# USB.net
KiCad netlist of a schematic drawn in Altium Designer
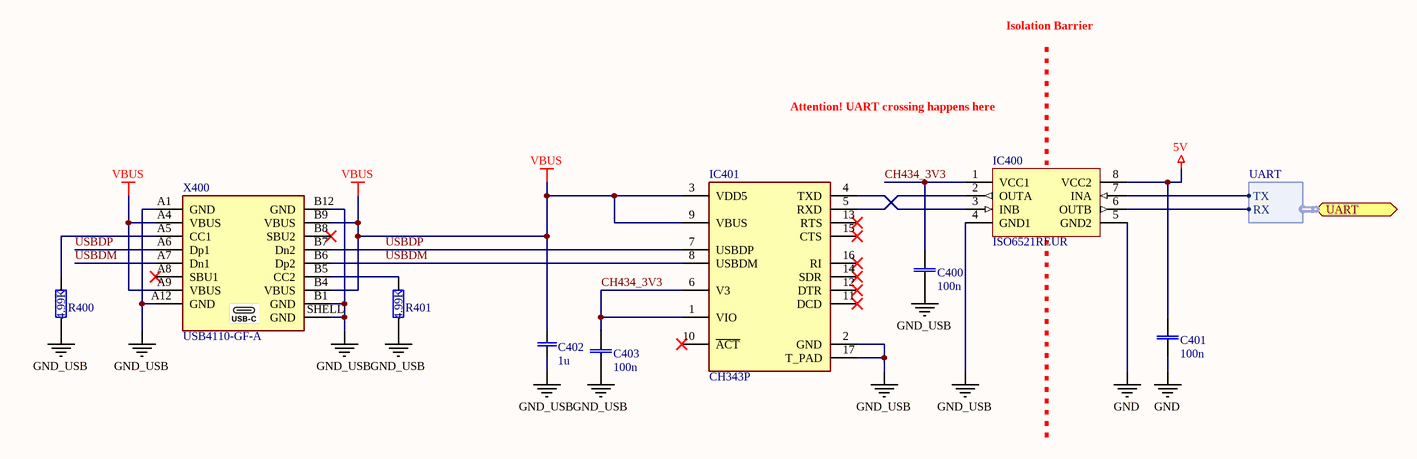
[diagram p0: USB.SchDoc]

(export (version "E")
  (design (tool "Eeschema 10.0.6"))
  (components
    (comp (ref "C400")
      (value "100n")
      (footprint "CAP0402")
      (fields (field (name "MPN") "CL05A104KA5NNNC") (field (name "TOLERANCE") "10%"))
      (libsource (lib "Schematic") (part "CL05A104KA5NNNC"))
    )
    (comp (ref "C401")
      (value "100n")
      (footprint "CAP0402")
      (fields (field (name "MPN") "CL05A104KA5NNNC") (field (name "TOLERANCE") "10%"))
      (libsource (lib "Schematic") (part "CL05A104KA5NNNC"))
    )
    (comp (ref "C402")
      (value "1u")
      (footprint "0603")
      (fields (field (name "PART NUMBER") "000088"))
      (libsource (lib "TychosLibrary") (part "Capacitor"))
    )
    (comp (ref "C403")
      (value "100n")
      (footprint "CAP0402")
      (fields (field (name "MPN") "CL05A104KA5NNNC") (field (name "TOLERANCE") "10%"))
      (libsource (lib "Schematic") (part "CL05A104KA5NNNC"))
    )
    (comp (ref "IC400")
      (value "ISO6521REUR")
      (footprint "VSON8(ISO6521REUR)")
      (libsource (lib "Schematic") (part "ISO6521REUR"))
    )
    (comp (ref "IC401")
      (value "CH343P")
      (footprint "QFN16_3X3")
      (fields (field (name "MANUFACTURER") "WCH") (field (name "JLCPCB PART #") "C2846043"))
      (libsource (lib "Schematic") (part "CH343P"))
    )
    (comp (ref "R400")
      (value "RC0402FR-074K99L")
      (footprint "RES0402")
      (libsource (lib "Passive") (part "RC0402FR-074K99L"))
    )
    (comp (ref "R401")
      (value "RC0402FR-074K99L")
      (footprint "RES0402")
      (libsource (lib "Passive") (part "RC0402FR-074K99L"))
    )
    (comp (ref "X400")
      (value "USB4110-GF-A")
      (footprint "USB4110")
      (libsource (lib "Schematic") (part "USB4110-GF-A"))
    )
  )
  (nets
    (net (code "2") (name "/CH434_3V3") (class "Default")
      (node (ref "C400") (pin "1") (pinfunction "1_1") (pintype "passive"))
      (node (ref "C403") (pin "1") (pinfunction "1_1") (pintype "passive"))
      (node (ref "IC400") (pin "1") (pinfunction "VCC1_1") (pintype "power_in"))
      (node (ref "IC401") (pin "1") (pinfunction "VIO_1") (pintype "passive"))
      (node (ref "IC401") (pin "6") (pinfunction "V3_6") (pintype "passive"))
    )
    (net (code "3") (name "/RX") (class "Default")
      (node (ref "IC400") (pin "6") (pinfunction "OUTB_6") (pintype "output"))
    )
    (net (code "4") (name "/TX") (class "Default")
      (node (ref "IC400") (pin "7") (pinfunction "INA_7") (pintype "input"))
    )
    (net (code "5") (name "/USBDM") (class "Default")
      (node (ref "IC401") (pin "8") (pinfunction "USBDM_8") (pintype "passive"))
      (node (ref "X400") (pin "A7") (pinfunction "Dn1_A7") (pintype "passive"))
      (node (ref "X400") (pin "B6") (pinfunction "Dp2_B6") (pintype "passive"))
    )
    (net (code "6") (name "/USBDP") (class "Default")
      (node (ref "IC401") (pin "7") (pinfunction "USBDP_7") (pintype "passive"))
      (node (ref "X400") (pin "A6") (pinfunction "Dp1_A6") (pintype "passive"))
      (node (ref "X400") (pin "B7") (pinfunction "Dn2_B7") (pintype "passive"))
    )
    (net (code "8") (name "5V") (class "Default")
      (node (ref "C401") (pin "1") (pinfunction "1_1") (pintype "passive"))
      (node (ref "IC400") (pin "8") (pinfunction "VCC2_8") (pintype "power_in"))
    )
    (net (code "9") (name "GND") (class "Default")
      (node (ref "C401") (pin "2") (pinfunction "2_2") (pintype "passive"))
      (node (ref "IC400") (pin "5") (pinfunction "GND2_5") (pintype "passive"))
    )
    (net (code "10") (name "GND_USB") (class "Default")
      (node (ref "C400") (pin "2") (pinfunction "2_2") (pintype "passive"))
      (node (ref "C402") (pin "1") (pinfunction "1_1") (pintype "passive"))
      (node (ref "C403") (pin "2") (pinfunction "2_2") (pintype "passive"))
      (node (ref "IC400") (pin "4") (pinfunction "GND1_4") (pintype "passive"))
      (node (ref "IC401") (pin "17") (pinfunction "T_PAD_17") (pintype "passive"))
      (node (ref "IC401") (pin "2") (pinfunction "GND_2") (pintype "passive"))
      (node (ref "R400") (pin "1") (pinfunction "1_1") (pintype "passive"))
      (node (ref "R401") (pin "1") (pinfunction "1_1") (pintype "passive"))
      (node (ref "X400") (pin "A1") (pinfunction "GND_A1") (pintype "passive"))
      (node (ref "X400") (pin "A12") (pinfunction "GND_A12") (pintype "passive"))
      (node (ref "X400") (pin "B1") (pinfunction "GND_B1") (pintype "passive"))
      (node (ref "X400") (pin "B12") (pinfunction "GND_B12") (pintype "passive"))
      (node (ref "X400") (pin "SHELL") (pinfunction "GND_SHELL") (pintype "passive"))
    )
    (net (code "11") (name "Net-(IC400-INB)") (class "Default")
      (node (ref "IC400") (pin "3") (pinfunction "INB_3") (pintype "input"))
      (node (ref "IC401") (pin "4") (pinfunction "TXD_4") (pintype "passive"))
    )
    (net (code "12") (name "Net-(IC400-OUTA)") (class "Default")
      (node (ref "IC400") (pin "2") (pinfunction "OUTA_2") (pintype "output"))
      (node (ref "IC401") (pin "5") (pinfunction "RXD_5") (pintype "passive"))
    )
    (net (code "13") (name "Net-(X400-CC1)") (class "Default")
      (node (ref "R400") (pin "2") (pinfunction "2_2") (pintype "passive"))
      (node (ref "X400") (pin "A5") (pinfunction "CC1_A5") (pintype "passive"))
    )
    (net (code "14") (name "Net-(X400-CC2)") (class "Default")
      (node (ref "R401") (pin "2") (pinfunction "2_2") (pintype "passive"))
      (node (ref "X400") (pin "B5") (pinfunction "CC2_B5") (pintype "passive"))
    )
    (net (code "15") (name "VBUS") (class "Default")
      (node (ref "C402") (pin "2") (pinfunction "2_2") (pintype "passive"))
      (node (ref "IC401") (pin "3") (pinfunction "VDD5_3") (pintype "passive"))
      (node (ref "IC401") (pin "9") (pinfunction "VBUS_9") (pintype "passive"))
      (node (ref "X400") (pin "A4") (pinfunction "VBUS_A4") (pintype "passive"))
      (node (ref "X400") (pin "A9") (pinfunction "VBUS_A9") (pintype "passive"))
      (node (ref "X400") (pin "B4") (pinfunction "VBUS_B4") (pintype "passive"))
      (node (ref "X400") (pin "B9") (pinfunction "VBUS_B9") (pintype "passive"))
    )
    (net (code "16") (name "unconnected-(IC401-CTS-Pad15)") (class "Default")
      (node (ref "IC401") (pin "15") (pinfunction "CTS_15") (pintype "passive+no_connect"))
    )
    (net (code "17") (name "unconnected-(IC401-DCD-Pad11)") (class "Default")
      (node (ref "IC401") (pin "11") (pinfunction "DCD_11") (pintype "passive+no_connect"))
    )
    (net (code "18") (name "unconnected-(IC401-DTR-Pad12)") (class "Default")
      (node (ref "IC401") (pin "12") (pinfunction "DTR_12") (pintype "passive+no_connect"))
    )
    (net (code "19") (name "unconnected-(IC401-RI-Pad16)") (class "Default")
      (node (ref "IC401") (pin "16") (pinfunction "RI_16") (pintype "passive+no_connect"))
    )
    (net (code "20") (name "unconnected-(IC401-RTS-Pad13)") (class "Default")
      (node (ref "IC401") (pin "13") (pinfunction "RTS_13") (pintype "passive+no_connect"))
    )
    (net (code "21") (name "unconnected-(IC401-SDR-Pad14)") (class "Default")
      (node (ref "IC401") (pin "14") (pinfunction "SDR_14") (pintype "passive+no_connect"))
    )
    (net (code "22") (name "unconnected-(IC401-~{ACT}-Pad10)") (class "Default")
      (node (ref "IC401") (pin "10") (pinfunction "~{ACT}_10") (pintype "passive+no_connect"))
    )
    (net (code "23") (name "unconnected-(X400-SBU1-PadA8)") (class "Default")
      (node (ref "X400") (pin "A8") (pinfunction "SBU1_A8") (pintype "passive+no_connect"))
    )
    (net (code "24") (name "unconnected-(X400-SBU2-PadB8)") (class "Default")
      (node (ref "X400") (pin "B8") (pinfunction "SBU2_B8") (pintype "passive+no_connect"))
    )
  )
)
